# gamecontroller_Teensy__1_3.net
KiCad netlist of a schematic drawn in EAGLE
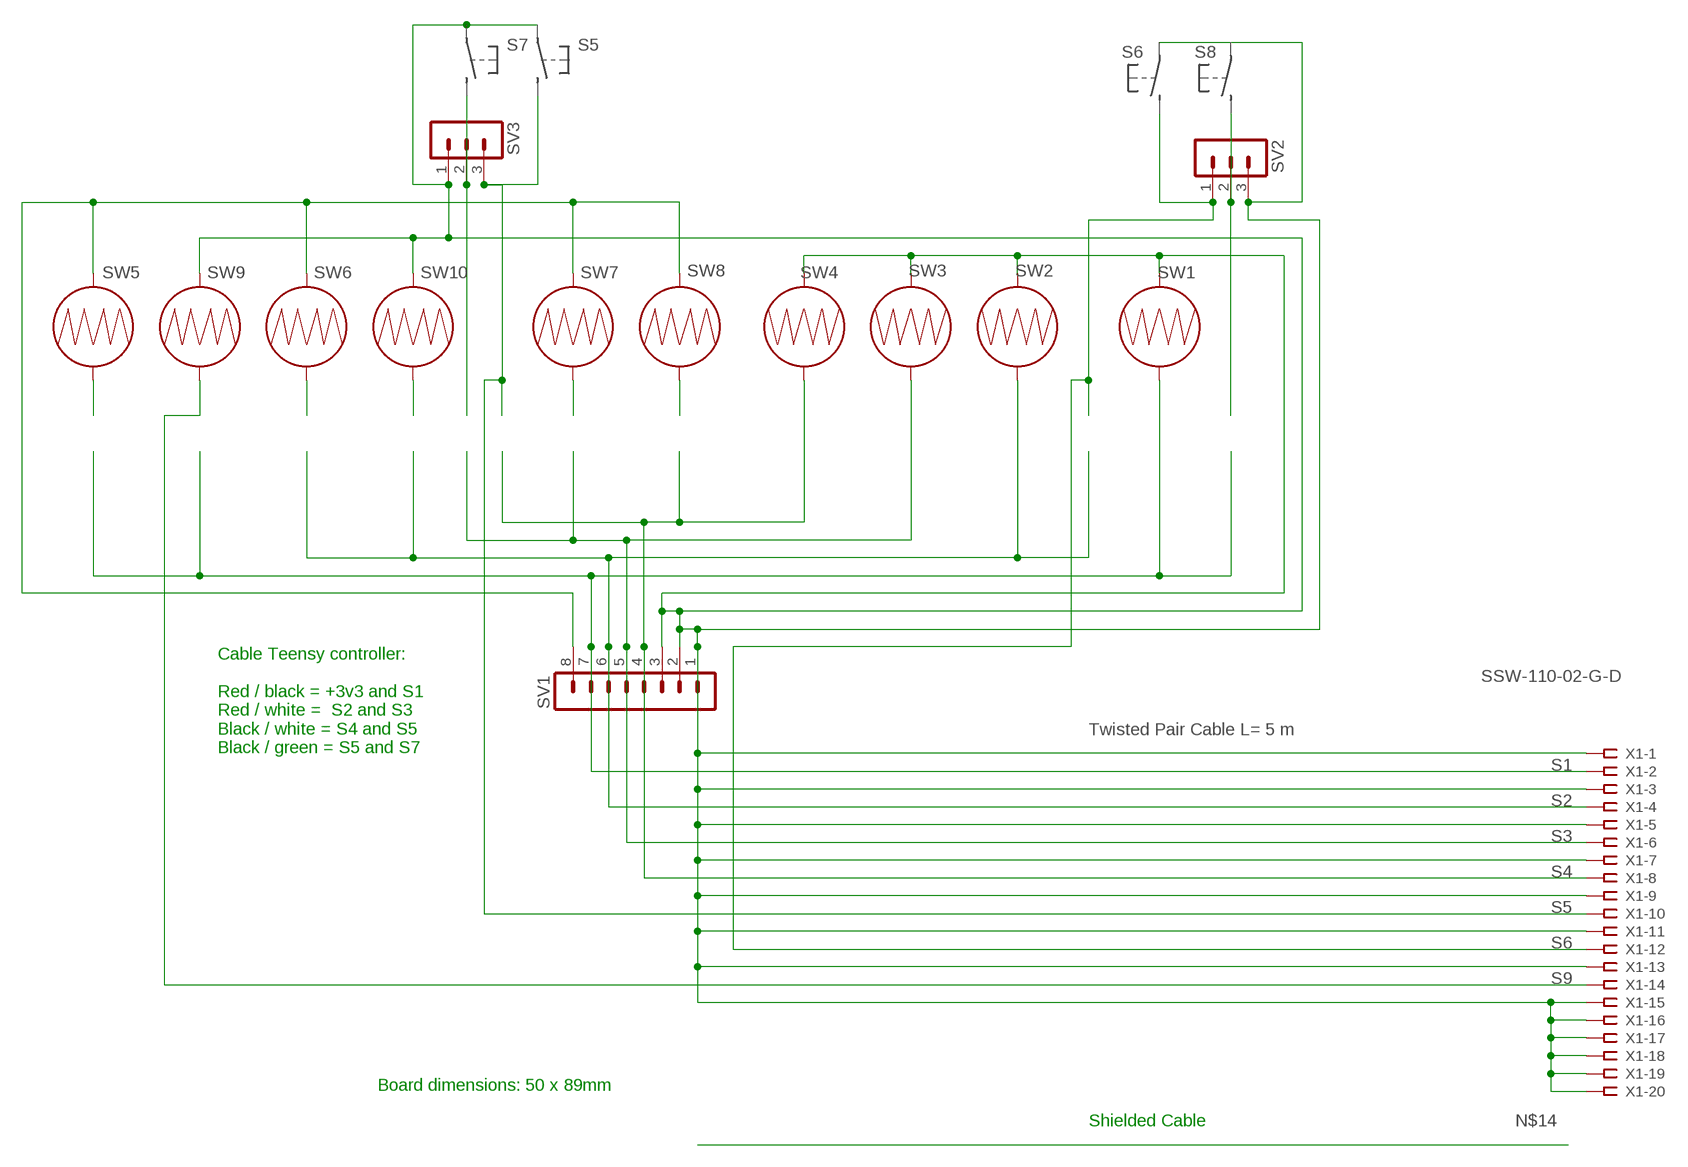
[diagram p0: schematic, sheet 1, part 1 of 2]
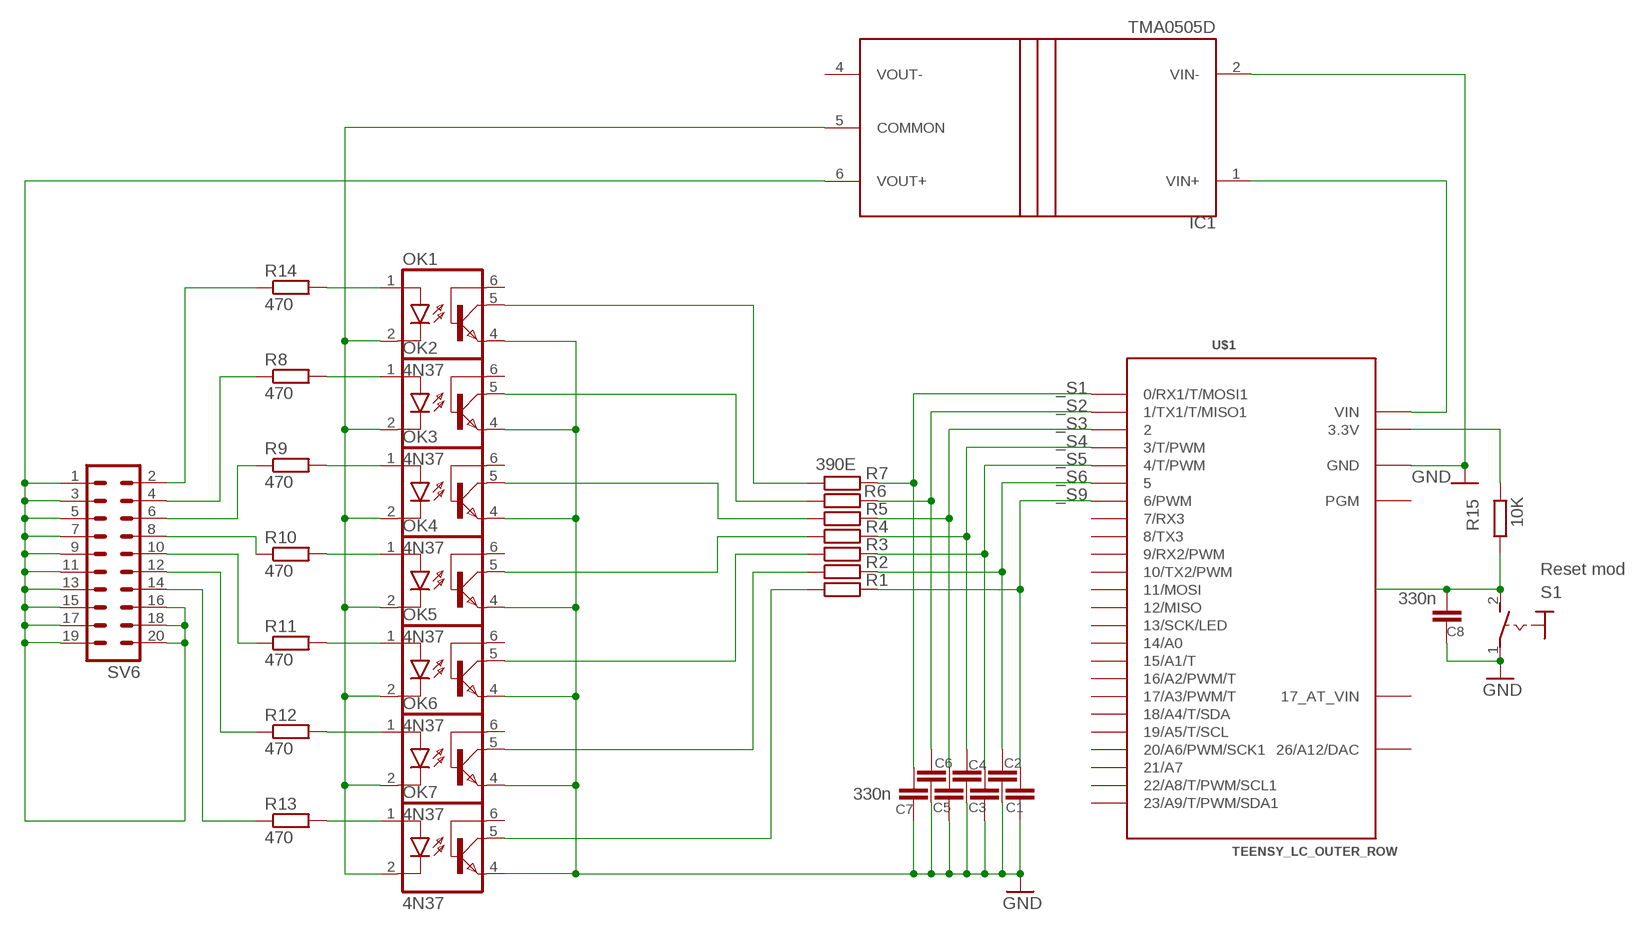
[diagram p1: schematic, sheet 1, part 2 of 2]

(export (version "E")
  (design (tool "Eeschema 10.0.6"))
  (components
    (comp (ref "C1")
      (value "C-EU025-025X050")
      (footprint "eagle-import:C025-025X050")
      (libsource (lib "eagle-import") (part "C-EU025-025X050"))
    )
    (comp (ref "C2")
      (value "C-EU025-025X050")
      (footprint "eagle-import:C025-025X050")
      (libsource (lib "eagle-import") (part "C-EU025-025X050"))
    )
    (comp (ref "C3")
      (value "C-EU025-025X050")
      (footprint "eagle-import:C025-025X050")
      (libsource (lib "eagle-import") (part "C-EU025-025X050"))
    )
    (comp (ref "C4")
      (value "C-EU025-025X050")
      (footprint "eagle-import:C025-025X050")
      (libsource (lib "eagle-import") (part "C-EU025-025X050"))
    )
    (comp (ref "C5")
      (value "C-EU025-025X050")
      (footprint "eagle-import:C025-025X050")
      (libsource (lib "eagle-import") (part "C-EU025-025X050"))
    )
    (comp (ref "C6")
      (value "C-EU025-025X050")
      (footprint "eagle-import:C025-025X050")
      (libsource (lib "eagle-import") (part "C-EU025-025X050"))
    )
    (comp (ref "C7")
      (value "330n")
      (footprint "eagle-import:C025-025X050")
      (libsource (lib "eagle-import") (part "C-EU025-025X050"))
    )
    (comp (ref "C8")
      (value "330n")
      (footprint "eagle-import:C025-025X050")
      (libsource (lib "eagle-import") (part "C-EU025-025X050"))
    )
    (comp (ref "IC1")
      (value "TMA0505D")
      (footprint "eagle-import:SIP7")
      (libsource (lib "eagle-import") (part "TMA0505D"))
    )
    (comp (ref "OK1")
      (value "4N37")
      (footprint "eagle-import:DIL06")
      (fields (field (name "MF") "FAIRCHILD SEMICONDUCTOR"))
      (libsource (lib "eagle-import") (part "4N37"))
    )
    (comp (ref "OK2")
      (value "4N37")
      (footprint "eagle-import:DIL06")
      (fields (field (name "MF") "FAIRCHILD SEMICONDUCTOR"))
      (libsource (lib "eagle-import") (part "4N37"))
    )
    (comp (ref "OK3")
      (value "4N37")
      (footprint "eagle-import:DIL06")
      (fields (field (name "MF") "FAIRCHILD SEMICONDUCTOR"))
      (libsource (lib "eagle-import") (part "4N37"))
    )
    (comp (ref "OK4")
      (value "4N37")
      (footprint "eagle-import:DIL06")
      (fields (field (name "MF") "FAIRCHILD SEMICONDUCTOR"))
      (libsource (lib "eagle-import") (part "4N37"))
    )
    (comp (ref "OK5")
      (value "4N37")
      (footprint "eagle-import:DIL06")
      (fields (field (name "MF") "FAIRCHILD SEMICONDUCTOR"))
      (libsource (lib "eagle-import") (part "4N37"))
    )
    (comp (ref "OK6")
      (value "4N37")
      (footprint "eagle-import:DIL06")
      (fields (field (name "MF") "FAIRCHILD SEMICONDUCTOR"))
      (libsource (lib "eagle-import") (part "4N37"))
    )
    (comp (ref "OK7")
      (value "4N37")
      (footprint "eagle-import:DIL06")
      (fields (field (name "MF") "FAIRCHILD SEMICONDUCTOR"))
      (libsource (lib "eagle-import") (part "4N37"))
    )
    (comp (ref "R1")
      (value "R-EU_0204/5")
      (footprint "eagle-import:0204_5")
      (libsource (lib "eagle-import") (part "R-EU_0204/5"))
    )
    (comp (ref "R2")
      (value "R-EU_0204/5")
      (footprint "eagle-import:0204_5")
      (libsource (lib "eagle-import") (part "R-EU_0204/5"))
    )
    (comp (ref "R3")
      (value "R-EU_0204/5")
      (footprint "eagle-import:0204_5")
      (libsource (lib "eagle-import") (part "R-EU_0204/5"))
    )
    (comp (ref "R4")
      (value "R-EU_0204/5")
      (footprint "eagle-import:0204_5")
      (libsource (lib "eagle-import") (part "R-EU_0204/5"))
    )
    (comp (ref "R5")
      (value "R-EU_0204/5")
      (footprint "eagle-import:0204_5")
      (libsource (lib "eagle-import") (part "R-EU_0204/5"))
    )
    (comp (ref "R6")
      (value "R-EU_0204/5")
      (footprint "eagle-import:0204_5")
      (libsource (lib "eagle-import") (part "R-EU_0204/5"))
    )
    (comp (ref "R7")
      (value "390E")
      (footprint "eagle-import:0204_5")
      (libsource (lib "eagle-import") (part "R-EU_0204/5"))
    )
    (comp (ref "R8")
      (value "470")
      (footprint "eagle-import:0204_5")
      (libsource (lib "eagle-import") (part "R-EU_0204/5"))
    )
    (comp (ref "R9")
      (value "470")
      (footprint "eagle-import:0204_5")
      (libsource (lib "eagle-import") (part "R-EU_0204/5"))
    )
    (comp (ref "R10")
      (value "470")
      (footprint "eagle-import:0204_5")
      (libsource (lib "eagle-import") (part "R-EU_0204/5"))
    )
    (comp (ref "R11")
      (value "470")
      (footprint "eagle-import:0204_5")
      (libsource (lib "eagle-import") (part "R-EU_0204/5"))
    )
    (comp (ref "R12")
      (value "470")
      (footprint "eagle-import:0204_5")
      (libsource (lib "eagle-import") (part "R-EU_0204/5"))
    )
    (comp (ref "R13")
      (value "470")
      (footprint "eagle-import:0204_5")
      (libsource (lib "eagle-import") (part "R-EU_0204/5"))
    )
    (comp (ref "R14")
      (value "470")
      (footprint "eagle-import:0204_5")
      (libsource (lib "eagle-import") (part "R-EU_0204/5"))
    )
    (comp (ref "R15")
      (value "10K")
      (footprint "eagle-import:0204_5")
      (libsource (lib "eagle-import") (part "R-EU_0204/5"))
    )
    (comp (ref "S1")
      (value "Reset mod")
      (footprint "eagle-import:MS243")
      (libsource (lib "eagle-import") (part "MS243"))
    )
    (comp (ref "SV1")
      (value "MA08-1")
      (footprint "eagle-import:MA08-1")
      (libsource (lib "eagle-import") (part "MA08-1"))
    )
    (comp (ref "SV2")
      (value "MA03-1")
      (footprint "eagle-import:MA03-1")
      (libsource (lib "eagle-import") (part "MA03-1"))
    )
    (comp (ref "SV3")
      (value "MA03-1")
      (footprint "eagle-import:MA03-1")
      (libsource (lib "eagle-import") (part "MA03-1"))
    )
    (comp (ref "SV6")
      (value "MA10-2W")
      (footprint "eagle-import:MA10-2W")
      (libsource (lib "eagle-import") (part "MA10-2W"))
    )
    (comp (ref "SW1")
      (value "BUTTON-CONDUCTIVESMD-0.1\"")
      (footprint "eagle-import:BUTTON-CONDUCTIVE-0.1")
      (libsource (lib "eagle-import") (part "BUTTON-CONDUCTIVESMD-0.1{dblquote}"))
    )
    (comp (ref "SW2")
      (value "BUTTON-CONDUCTIVESMD-0.1\"")
      (footprint "eagle-import:BUTTON-CONDUCTIVE-0.1")
      (libsource (lib "eagle-import") (part "BUTTON-CONDUCTIVESMD-0.1{dblquote}"))
    )
    (comp (ref "SW3")
      (value "BUTTON-CONDUCTIVESMD-0.1\"")
      (footprint "eagle-import:BUTTON-CONDUCTIVE-0.1")
      (libsource (lib "eagle-import") (part "BUTTON-CONDUCTIVESMD-0.1{dblquote}"))
    )
    (comp (ref "SW4")
      (value "BUTTON-CONDUCTIVESMD-0.1\"")
      (footprint "eagle-import:BUTTON-CONDUCTIVE-0.1")
      (libsource (lib "eagle-import") (part "BUTTON-CONDUCTIVESMD-0.1{dblquote}"))
    )
    (comp (ref "SW5")
      (value "BUTTON-CONDUCTIVESMD-0.1\"")
      (footprint "eagle-import:BUTTON-CONDUCTIVE-0.1")
      (libsource (lib "eagle-import") (part "BUTTON-CONDUCTIVESMD-0.1{dblquote}"))
    )
    (comp (ref "SW6")
      (value "BUTTON-CONDUCTIVESMD-0.1\"")
      (footprint "eagle-import:BUTTON-CONDUCTIVE-0.1")
      (libsource (lib "eagle-import") (part "BUTTON-CONDUCTIVESMD-0.1{dblquote}"))
    )
    (comp (ref "SW7")
      (value "BUTTON-CONDUCTIVESMD-0.1\"")
      (footprint "eagle-import:BUTTON-CONDUCTIVE-0.1")
      (libsource (lib "eagle-import") (part "BUTTON-CONDUCTIVESMD-0.1{dblquote}"))
    )
    (comp (ref "SW8")
      (value "BUTTON-CONDUCTIVESMD-0.1\"")
      (footprint "eagle-import:BUTTON-CONDUCTIVE-0.1")
      (libsource (lib "eagle-import") (part "BUTTON-CONDUCTIVESMD-0.1{dblquote}"))
    )
    (comp (ref "SW9")
      (value "BUTTON-CONDUCTIVESMD-0.1\"")
      (footprint "eagle-import:BUTTON-CONDUCTIVE-0.1")
      (libsource (lib "eagle-import") (part "BUTTON-CONDUCTIVESMD-0.1{dblquote}"))
    )
    (comp (ref "SW10")
      (value "BUTTON-CONDUCTIVESMD-0.1\"")
      (footprint "eagle-import:BUTTON-CONDUCTIVE-0.1")
      (libsource (lib "eagle-import") (part "BUTTON-CONDUCTIVESMD-0.1{dblquote}"))
    )
    (comp (ref "U$1")
      (value "TEENSY_LC_OUTER_ROW")
      (footprint "eagle-import:TEENSY_3.0-3.2&LC_OUTER_ROW")
      (libsource (lib "eagle-import") (part "TEENSY_LC_OUTER_ROW"))
    )
    (comp (ref "X1")
      (value "SSW-110-02-G-D")
      (footprint "eagle-import:SSW-110-02-G-D")
      (fields (field (name "MF") "Samtec Inc."))
      (libsource (lib "eagle-import") (part "SSW-110-02-G-D"))
    )
  )
  (nets
    (net (code "1") (name "/26{slash}A12{slash}DAC") (class "Default")
      (node (ref "U$1") (pin "RESET/DAC") (pinfunction "26/A12/DAC_RESET/DAC") (pintype "power_in"))
    )
    (net (code "3") (name "/S1") (class "Default")
      (node (ref "SV1") (pin "7") (pinfunction "7_7") (pintype "passive"))
      (node (ref "SW1") (pin "1") (pinfunction "1_1") (pintype "passive"))
      (node (ref "X1") (pin "2") (pinfunction "1_2") (pintype "passive"))
    )
    (net (code "4") (name "/S2") (class "Default")
      (node (ref "SV1") (pin "6") (pinfunction "6_6") (pintype "passive"))
      (node (ref "SW2") (pin "1") (pinfunction "1_1") (pintype "passive"))
      (node (ref "X1") (pin "4") (pinfunction "1_4") (pintype "passive"))
    )
    (net (code "5") (name "/S3") (class "Default")
      (node (ref "SV1") (pin "5") (pinfunction "5_5") (pintype "passive"))
      (node (ref "SW3") (pin "1") (pinfunction "1_1") (pintype "passive"))
      (node (ref "X1") (pin "6") (pinfunction "1_6") (pintype "passive"))
    )
    (net (code "6") (name "/S4") (class "Default")
      (node (ref "SV1") (pin "4") (pinfunction "4_4") (pintype "passive"))
      (node (ref "SW4") (pin "1") (pinfunction "1_1") (pintype "passive"))
      (node (ref "X1") (pin "8") (pinfunction "1_8") (pintype "passive"))
    )
    (net (code "7") (name "/S5") (class "Default")
      (node (ref "SV3") (pin "3") (pinfunction "3_3") (pintype "passive"))
      (node (ref "X1") (pin "10") (pinfunction "1_10") (pintype "passive"))
    )
    (net (code "8") (name "/S6") (class "Default")
      (node (ref "SV2") (pin "1") (pinfunction "1_1") (pintype "passive"))
      (node (ref "X1") (pin "12") (pinfunction "1_12") (pintype "passive"))
    )
    (net (code "9") (name "/S9") (class "Default")
      (node (ref "SW9") (pin "2") (pinfunction "2_2") (pintype "passive"))
      (node (ref "X1") (pin "14") (pinfunction "1_14") (pintype "passive"))
    )
    (net (code "10") (name "/VOUT-") (class "Default")
      (node (ref "IC1") (pin "4") (pinfunction "VOUT-_4") (pintype "power_in"))
    )
    (net (code "11") (name "/_S1") (class "Default")
      (node (ref "C7") (pin "1") (pinfunction "1_1") (pintype "passive"))
      (node (ref "R7") (pin "2") (pinfunction "2_2") (pintype "passive"))
      (node (ref "U$1") (pin "0") (pinfunction "0/RX1/T/MOSI1_0") (pintype "bidirectional"))
    )
    (net (code "12") (name "/_S2") (class "Default")
      (node (ref "C6") (pin "1") (pinfunction "1_1") (pintype "passive"))
      (node (ref "R6") (pin "2") (pinfunction "2_2") (pintype "passive"))
      (node (ref "U$1") (pin "1") (pinfunction "1/TX1/T/MISO1_1") (pintype "bidirectional"))
    )
    (net (code "13") (name "/_S3") (class "Default")
      (node (ref "C5") (pin "1") (pinfunction "1_1") (pintype "passive"))
      (node (ref "R5") (pin "2") (pinfunction "2_2") (pintype "passive"))
      (node (ref "U$1") (pin "2") (pinfunction "2_2") (pintype "bidirectional"))
    )
    (net (code "14") (name "/_S4") (class "Default")
      (node (ref "C4") (pin "1") (pinfunction "1_1") (pintype "passive"))
      (node (ref "R4") (pin "2") (pinfunction "2_2") (pintype "passive"))
      (node (ref "U$1") (pin "3") (pinfunction "3/T/PWM_3") (pintype "bidirectional"))
    )
    (net (code "15") (name "/_S5") (class "Default")
      (node (ref "C3") (pin "1") (pinfunction "1_1") (pintype "passive"))
      (node (ref "R3") (pin "2") (pinfunction "2_2") (pintype "passive"))
      (node (ref "U$1") (pin "4") (pinfunction "4/T/PWM_4") (pintype "bidirectional"))
    )
    (net (code "16") (name "/_S6") (class "Default")
      (node (ref "C2") (pin "1") (pinfunction "1_1") (pintype "passive"))
      (node (ref "R2") (pin "2") (pinfunction "2_2") (pintype "passive"))
      (node (ref "U$1") (pin "5") (pinfunction "5_5") (pintype "bidirectional"))
    )
    (net (code "17") (name "/_S9") (class "Default")
      (node (ref "C1") (pin "1") (pinfunction "1_1") (pintype "passive"))
      (node (ref "R1") (pin "2") (pinfunction "2_2") (pintype "passive"))
      (node (ref "U$1") (pin "6") (pinfunction "6/PWM_6") (pintype "bidirectional"))
    )
    (net (code "18") (name "GND") (class "Default")
      (node (ref "C1") (pin "2") (pinfunction "2_2") (pintype "passive"))
      (node (ref "C2") (pin "2") (pinfunction "2_2") (pintype "passive"))
      (node (ref "C3") (pin "2") (pinfunction "2_2") (pintype "passive"))
      (node (ref "C4") (pin "2") (pinfunction "2_2") (pintype "passive"))
      (node (ref "C5") (pin "2") (pinfunction "2_2") (pintype "passive"))
      (node (ref "C6") (pin "2") (pinfunction "2_2") (pintype "passive"))
      (node (ref "C7") (pin "2") (pinfunction "2_2") (pintype "passive"))
      (node (ref "C8") (pin "2") (pinfunction "2_2") (pintype "passive"))
      (node (ref "IC1") (pin "2") (pinfunction "VIN-_2") (pintype "power_in"))
      (node (ref "OK1") (pin "4") (pinfunction "EMI_4") (pintype "passive"))
      (node (ref "OK2") (pin "4") (pinfunction "EMI_4") (pintype "passive"))
      (node (ref "OK3") (pin "4") (pinfunction "EMI_4") (pintype "passive"))
      (node (ref "OK4") (pin "4") (pinfunction "EMI_4") (pintype "passive"))
      (node (ref "OK5") (pin "4") (pinfunction "EMI_4") (pintype "passive"))
      (node (ref "OK6") (pin "4") (pinfunction "EMI_4") (pintype "passive"))
      (node (ref "OK7") (pin "4") (pinfunction "EMI_4") (pintype "passive"))
      (node (ref "S1") (pin "1") (pinfunction "P_1") (pintype "passive"))
      (node (ref "U$1") (pin "AGND") (pinfunction "GND_AGND") (pintype "power_in"))
      (node (ref "U$1") (pin "GND") (pinfunction "GND_GND") (pintype "power_in"))
      (node (ref "U$1") (pin "GND1") (pinfunction "GND_GND1") (pintype "power_in"))
    )
    (net (code "19") (name "Net-(IC1-COMMON)") (class "Default")
      (node (ref "IC1") (pin "5") (pinfunction "COMMON_5") (pintype "power_in"))
      (node (ref "OK1") (pin "2") (pinfunction "C_2") (pintype "passive"))
      (node (ref "OK2") (pin "2") (pinfunction "C_2") (pintype "passive"))
      (node (ref "OK3") (pin "2") (pinfunction "C_2") (pintype "passive"))
      (node (ref "OK4") (pin "2") (pinfunction "C_2") (pintype "passive"))
      (node (ref "OK5") (pin "2") (pinfunction "C_2") (pintype "passive"))
      (node (ref "OK6") (pin "2") (pinfunction "C_2") (pintype "passive"))
      (node (ref "OK7") (pin "2") (pinfunction "C_2") (pintype "passive"))
    )
    (net (code "20") (name "Net-(IC1-VIN+)") (class "Default")
      (node (ref "IC1") (pin "1") (pinfunction "VIN+_1") (pintype "power_in"))
      (node (ref "U$1") (pin "VIN") (pinfunction "VIN_VIN") (pintype "power_in"))
    )
    (net (code "21") (name "Net-(IC1-VOUT+)") (class "Default")
      (node (ref "IC1") (pin "6") (pinfunction "VOUT+_6") (pintype "power_in"))
      (node (ref "SV6") (pin "1") (pinfunction "1_1") (pintype "passive"))
      (node (ref "SV6") (pin "11") (pinfunction "11_11") (pintype "passive"))
      (node (ref "SV6") (pin "13") (pinfunction "13_13") (pintype "passive"))
      (node (ref "SV6") (pin "15") (pinfunction "15_15") (pintype "passive"))
      (node (ref "SV6") (pin "16") (pinfunction "16_16") (pintype "passive"))
      (node (ref "SV6") (pin "17") (pinfunction "17_17") (pintype "passive"))
      (node (ref "SV6") (pin "18") (pinfunction "18_18") (pintype "passive"))
      (node (ref "SV6") (pin "19") (pinfunction "19_19") (pintype "passive"))
      (node (ref "SV6") (pin "20") (pinfunction "20_20") (pintype "passive"))
      (node (ref "SV6") (pin "3") (pinfunction "3_3") (pintype "passive"))
      (node (ref "SV6") (pin "5") (pinfunction "5_5") (pintype "passive"))
      (node (ref "SV6") (pin "7") (pinfunction "7_7") (pintype "passive"))
      (node (ref "SV6") (pin "9") (pinfunction "9_9") (pintype "passive"))
    )
    (net (code "22") (name "Net-(OK1-A)") (class "Default")
      (node (ref "OK1") (pin "1") (pinfunction "A_1") (pintype "passive"))
      (node (ref "R14") (pin "2") (pinfunction "2_2") (pintype "passive"))
    )
    (net (code "23") (name "Net-(OK1-COL)") (class "Default")
      (node (ref "OK1") (pin "5") (pinfunction "COL_5") (pintype "passive"))
      (node (ref "R7") (pin "1") (pinfunction "1_1") (pintype "passive"))
    )
    (net (code "24") (name "Net-(OK2-A)") (class "Default")
      (node (ref "OK2") (pin "1") (pinfunction "A_1") (pintype "passive"))
      (node (ref "R8") (pin "2") (pinfunction "2_2") (pintype "passive"))
    )
    (net (code "25") (name "Net-(OK2-COL)") (class "Default")
      (node (ref "OK2") (pin "5") (pinfunction "COL_5") (pintype "passive"))
      (node (ref "R6") (pin "1") (pinfunction "1_1") (pintype "passive"))
    )
    (net (code "26") (name "Net-(OK3-A)") (class "Default")
      (node (ref "OK3") (pin "1") (pinfunction "A_1") (pintype "passive"))
      (node (ref "R9") (pin "2") (pinfunction "2_2") (pintype "passive"))
    )
    (net (code "27") (name "Net-(OK3-COL)") (class "Default")
      (node (ref "OK3") (pin "5") (pinfunction "COL_5") (pintype "passive"))
      (node (ref "R5") (pin "1") (pinfunction "1_1") (pintype "passive"))
    )
    (net (code "28") (name "Net-(OK4-A)") (class "Default")
      (node (ref "OK4") (pin "1") (pinfunction "A_1") (pintype "passive"))
      (node (ref "R10") (pin "2") (pinfunction "2_2") (pintype "passive"))
    )
    (net (code "29") (name "Net-(OK4-COL)") (class "Default")
      (node (ref "OK4") (pin "5") (pinfunction "COL_5") (pintype "passive"))
      (node (ref "R4") (pin "1") (pinfunction "1_1") (pintype "passive"))
    )
    (net (code "30") (name "Net-(OK5-A)") (class "Default")
      (node (ref "OK5") (pin "1") (pinfunction "A_1") (pintype "passive"))
      (node (ref "R11") (pin "2") (pinfunction "2_2") (pintype "passive"))
    )
    (net (code "31") (name "Net-(OK5-COL)") (class "Default")
      (node (ref "OK5") (pin "5") (pinfunction "COL_5") (pintype "passive"))
      (node (ref "R3") (pin "1") (pinfunction "1_1") (pintype "passive"))
    )
    (net (code "32") (name "Net-(OK6-A)") (class "Default")
      (node (ref "OK6") (pin "1") (pinfunction "A_1") (pintype "passive"))
      (node (ref "R12") (pin "2") (pinfunction "2_2") (pintype "passive"))
    )
    (net (code "33") (name "Net-(OK6-COL)") (class "Default")
      (node (ref "OK6") (pin "5") (pinfunction "COL_5") (pintype "passive"))
      (node (ref "R2") (pin "1") (pinfunction "1_1") (pintype "passive"))
    )
    (net (code "34") (name "Net-(OK7-A)") (class "Default")
      (node (ref "OK7") (pin "1") (pinfunction "A_1") (pintype "passive"))
      (node (ref "R13") (pin "2") (pinfunction "2_2") (pintype "passive"))
    )
    (net (code "35") (name "Net-(OK7-COL)") (class "Default")
      (node (ref "OK7") (pin "5") (pinfunction "COL_5") (pintype "passive"))
      (node (ref "R1") (pin "1") (pinfunction "1_1") (pintype "passive"))
    )
    (net (code "36") (name "Net-(R8-Pad1)") (class "Default")
      (node (ref "R8") (pin "1") (pinfunction "1_1") (pintype "passive"))
      (node (ref "SV6") (pin "4") (pinfunction "4_4") (pintype "passive"))
    )
    (net (code "37") (name "Net-(R9-Pad1)") (class "Default")
      (node (ref "R9") (pin "1") (pinfunction "1_1") (pintype "passive"))
      (node (ref "SV6") (pin "6") (pinfunction "6_6") (pintype "passive"))
    )
    (net (code "38") (name "Net-(R10-Pad1)") (class "Default")
      (node (ref "R10") (pin "1") (pinfunction "1_1") (pintype "passive"))
      (node (ref "SV6") (pin "8") (pinfunction "8_8") (pintype "passive"))
    )
    (net (code "39") (name "Net-(R11-Pad1)") (class "Default")
      (node (ref "R11") (pin "1") (pinfunction "1_1") (pintype "passive"))
      (node (ref "SV6") (pin "10") (pinfunction "10_10") (pintype "passive"))
    )
    (net (code "40") (name "Net-(R12-Pad1)") (class "Default")
      (node (ref "R12") (pin "1") (pinfunction "1_1") (pintype "passive"))
      (node (ref "SV6") (pin "12") (pinfunction "12_12") (pintype "passive"))
    )
    (net (code "41") (name "Net-(R13-Pad1)") (class "Default")
      (node (ref "R13") (pin "1") (pinfunction "1_1") (pintype "passive"))
      (node (ref "SV6") (pin "14") (pinfunction "14_14") (pintype "passive"))
    )
    (net (code "42") (name "Net-(R14-Pad1)") (class "Default")
      (node (ref "R14") (pin "1") (pinfunction "1_1") (pintype "passive"))
      (node (ref "SV6") (pin "2") (pinfunction "2_2") (pintype "passive"))
    )
    (net (code "43") (name "Net-(R15-Pad2)") (class "Default")
      (node (ref "R15") (pin "2") (pinfunction "2_2") (pintype "passive"))
      (node (ref "U$1") (pin "3.3V") (pinfunction "3.3V_3.3V") (pintype "power_in"))
      (node (ref "U$1") (pin "3.3V1") (pinfunction "3.3V_3.3V1") (pintype "power_in"))
    )
    (net (code "44") (name "Net-(S1-S)") (class "Default")
      (node (ref "C8") (pin "1") (pinfunction "1_1") (pintype "passive"))
      (node (ref "R15") (pin "1") (pinfunction "1_1") (pintype "passive"))
      (node (ref "S1") (pin "2") (pinfunction "S_2") (pintype "passive"))
    )
    (net (code "45") (name "Net-(SV1-Pad8)") (class "Default")
      (node (ref "SV1") (pin "8") (pinfunction "8_8") (pintype "passive"))
      (node (ref "SW5") (pin "1") (pinfunction "1_1") (pintype "passive"))
      (node (ref "SW6") (pin "1") (pinfunction "1_1") (pintype "passive"))
      (node (ref "SW7") (pin "1") (pinfunction "1_1") (pintype "passive"))
      (node (ref "SW8") (pin "1") (pinfunction "1_1") (pintype "passive"))
    )
    (net (code "46") (name "Net-(X1C-1)") (class "Default")
      (node (ref "SV1") (pin "1") (pinfunction "1_1") (pintype "passive"))
      (node (ref "SV1") (pin "2") (pinfunction "2_2") (pintype "passive"))
      (node (ref "SV1") (pin "3") (pinfunction "3_3") (pintype "passive"))
      (node (ref "SV2") (pin "3") (pinfunction "3_3") (pintype "passive"))
      (node (ref "SV3") (pin "1") (pinfunction "1_1") (pintype "passive"))
      (node (ref "SW1") (pin "2") (pinfunction "2_2") (pintype "passive"))
      (node (ref "SW10") (pin "1") (pinfunction "1_1") (pintype "passive"))
      (node (ref "SW2") (pin "2") (pinfunction "2_2") (pintype "passive"))
      (node (ref "SW3") (pin "2") (pinfunction "2_2") (pintype "passive"))
      (node (ref "SW4") (pin "2") (pinfunction "2_2") (pintype "passive"))
      (node (ref "SW9") (pin "1") (pinfunction "1_1") (pintype "passive"))
      (node (ref "X1") (pin "1") (pinfunction "1_1") (pintype "passive"))
      (node (ref "X1") (pin "11") (pinfunction "1_11") (pintype "passive"))
      (node (ref "X1") (pin "13") (pinfunction "1_13") (pintype "passive"))
      (node (ref "X1") (pin "15") (pinfunction "1_15") (pintype "passive"))
      (node (ref "X1") (pin "16") (pinfunction "1_16") (pintype "passive"))
      (node (ref "X1") (pin "17") (pinfunction "1_17") (pintype "passive"))
      (node (ref "X1") (pin "18") (pinfunction "1_18") (pintype "passive"))
      (node (ref "X1") (pin "19") (pinfunction "1_19") (pintype "passive"))
      (node (ref "X1") (pin "20") (pinfunction "1_20") (pintype "passive"))
      (node (ref "X1") (pin "3") (pinfunction "1_3") (pintype "passive"))
      (node (ref "X1") (pin "5") (pinfunction "1_5") (pintype "passive"))
      (node (ref "X1") (pin "7") (pinfunction "1_7") (pintype "passive"))
      (node (ref "X1") (pin "9") (pinfunction "1_9") (pintype "passive"))
    )
    (net (code "47") (name "unconnected-(OK1-BAS-Pad6)") (class "Default")
      (node (ref "OK1") (pin "6") (pinfunction "BAS_6") (pintype "passive"))
    )
    (net (code "48") (name "unconnected-(OK2-BAS-Pad6)") (class "Default")
      (node (ref "OK2") (pin "6") (pinfunction "BAS_6") (pintype "passive"))
    )
    (net (code "49") (name "unconnected-(OK3-BAS-Pad6)") (class "Default")
      (node (ref "OK3") (pin "6") (pinfunction "BAS_6") (pintype "passive"))
    )
    (net (code "50") (name "unconnected-(OK4-BAS-Pad6)") (class "Default")
      (node (ref "OK4") (pin "6") (pinfunction "BAS_6") (pintype "passive"))
    )
    (net (code "51") (name "unconnected-(OK5-BAS-Pad6)") (class "Default")
      (node (ref "OK5") (pin "6") (pinfunction "BAS_6") (pintype "passive"))
    )
    (net (code "52") (name "unconnected-(OK6-BAS-Pad6)") (class "Default")
      (node (ref "OK6") (pin "6") (pinfunction "BAS_6") (pintype "passive"))
    )
    (net (code "53") (name "unconnected-(OK7-BAS-Pad6)") (class "Default")
      (node (ref "OK7") (pin "6") (pinfunction "BAS_6") (pintype "passive"))
    )
    (net (code "54") (name "unconnected-(SV2-Pad2)") (class "Default")
      (node (ref "SV2") (pin "2") (pinfunction "2_2") (pintype "passive"))
    )
    (net (code "55") (name "unconnected-(SV3-Pad2)") (class "Default")
      (node (ref "SV3") (pin "2") (pinfunction "2_2") (pintype "passive"))
    )
    (net (code "56") (name "unconnected-(SW5-Pad2)") (class "Default")
      (node (ref "SW5") (pin "2") (pinfunction "2_2") (pintype "passive"))
    )
    (net (code "57") (name "unconnected-(SW6-Pad2)") (class "Default")
      (node (ref "SW6") (pin "2") (pinfunction "2_2") (pintype "passive"))
    )
    (net (code "58") (name "unconnected-(SW7-Pad2)") (class "Default")
      (node (ref "SW7") (pin "2") (pinfunction "2_2") (pintype "passive"))
    )
    (net (code "59") (name "unconnected-(SW8-Pad2)") (class "Default")
      (node (ref "SW8") (pin "2") (pinfunction "2_2") (pintype "passive"))
    )
    (net (code "60") (name "unconnected-(SW10-Pad2)") (class "Default")
      (node (ref "SW10") (pin "2") (pinfunction "2_2") (pintype "passive"))
    )
    (net (code "61") (name "unconnected-(U$1-7{slash}RX3-Pad7)") (class "Default")
      (node (ref "U$1") (pin "7") (pinfunction "7/RX3_7") (pintype "bidirectional"))
    )
    (net (code "62") (name "unconnected-(U$1-8{slash}TX3-Pad8)") (class "Default")
      (node (ref "U$1") (pin "8") (pinfunction "8/TX3_8") (pintype "bidirectional"))
    )
    (net (code "63") (name "unconnected-(U$1-9{slash}RX2{slash}PWM-Pad9)") (class "Default")
      (node (ref "U$1") (pin "9") (pinfunction "9/RX2/PWM_9") (pintype "bidirectional"))
    )
    (net (code "64") (name "unconnected-(U$1-10{slash}TX2{slash}PWM-Pad10)") (class "Default")
      (node (ref "U$1") (pin "10") (pinfunction "10/TX2/PWM_10") (pintype "bidirectional"))
    )
    (net (code "65") (name "unconnected-(U$1-11{slash}MOSI-Pad11)") (class "Default")
      (node (ref "U$1") (pin "11") (pinfunction "11/MOSI_11") (pintype "bidirectional"))
    )
    (net (code "66") (name "unconnected-(U$1-12{slash}MISO-Pad12)") (class "Default")
      (node (ref "U$1") (pin "12") (pinfunction "12/MISO_12") (pintype "bidirectional"))
    )
    (net (code "67") (name "unconnected-(U$1-13{slash}SCK{slash}LED-Pad13)") (class "Default")
      (node (ref "U$1") (pin "13") (pinfunction "13/SCK/LED_13") (pintype "bidirectional"))
    )
    (net (code "68") (name "unconnected-(U$1-15{slash}A1{slash}T-Pad15{slash}A1)") (class "Default")
      (node (ref "U$1") (pin "15/A1") (pinfunction "15/A1/T_15/A1") (pintype "bidirectional"))
    )
    (net (code "69") (name "unconnected-(U$1-16{slash}A2{slash}PWM{slash}T-Pad16{slash}A2)") (class "Default")
      (node (ref "U$1") (pin "16/A2") (pinfunction "16/A2/PWM/T_16/A2") (pintype "bidirectional"))
    )
    (net (code "70") (name "unconnected-(U$1-17_AT_VIN-PadVBAT)") (class "Default")
      (node (ref "U$1") (pin "VBAT") (pinfunction "17_AT_VIN_VBAT") (pintype "bidirectional"))
    )
    (net (code "71") (name "unconnected-(U$1-17{slash}A3{slash}PWM{slash}T-Pad17{slash}A3)") (class "Default")
      (node (ref "U$1") (pin "17/A3") (pinfunction "17/A3/PWM/T_17/A3") (pintype "bidirectional"))
    )
    (net (code "72") (name "unconnected-(U$1-18{slash}A4{slash}T{slash}SDA-Pad18{slash}A4)") (class "Default")
      (node (ref "U$1") (pin "18/A4") (pinfunction "18/A4/T/SDA_18/A4") (pintype "bidirectional"))
    )
    (net (code "73") (name "unconnected-(U$1-19{slash}A5{slash}T{slash}SCL-Pad19{slash}A5)") (class "Default")
      (node (ref "U$1") (pin "19/A5") (pinfunction "19/A5/T/SCL_19/A5") (pintype "bidirectional"))
    )
    (net (code "74") (name "unconnected-(U$1-20{slash}A6{slash}PWM{slash}SCK1-Pad20{slash}A6)") (class "Default")
      (node (ref "U$1") (pin "20/A6") (pinfunction "20/A6/PWM/SCK1_20/A6") (pintype "bidirectional"))
    )
    (net (code "75") (name "unconnected-(U$1-22{slash}A8{slash}T{slash}PWM{slash}SCL1-Pad22{slash}A8)") (class "Default")
      (node (ref "U$1") (pin "22/A8") (pinfunction "22/A8/T/PWM/SCL1_22/A8") (pintype "bidirectional"))
    )
    (net (code "76") (name "unconnected-(U$1-23{slash}A9{slash}T{slash}PWM{slash}SDA1-Pad23{slash}A9)") (class "Default")
      (node (ref "U$1") (pin "23/A9") (pinfunction "23/A9/T/PWM/SDA1_23/A9") (pintype "bidirectional"))
    )
    (net (code "77") (name "unconnected-(U$1-Pad14{slash}A0)") (class "Default")
      (node (ref "U$1") (pin "14/A0") (pinfunction "14/A0_14/A0") (pintype "bidirectional"))
    )
    (net (code "78") (name "unconnected-(U$1-Pad21{slash}A7)") (class "Default")
      (node (ref "U$1") (pin "21/A7") (pinfunction "21/A7_21/A7") (pintype "bidirectional"))
    )
    (net (code "79") (name "unconnected-(U$1-PadPGM)") (class "Default")
      (node (ref "U$1") (pin "PGM") (pinfunction "PGM_PGM") (pintype "bidirectional"))
    )
  )
)
